# jussi.net
KiCad netlist of a schematic drawn in EAGLE
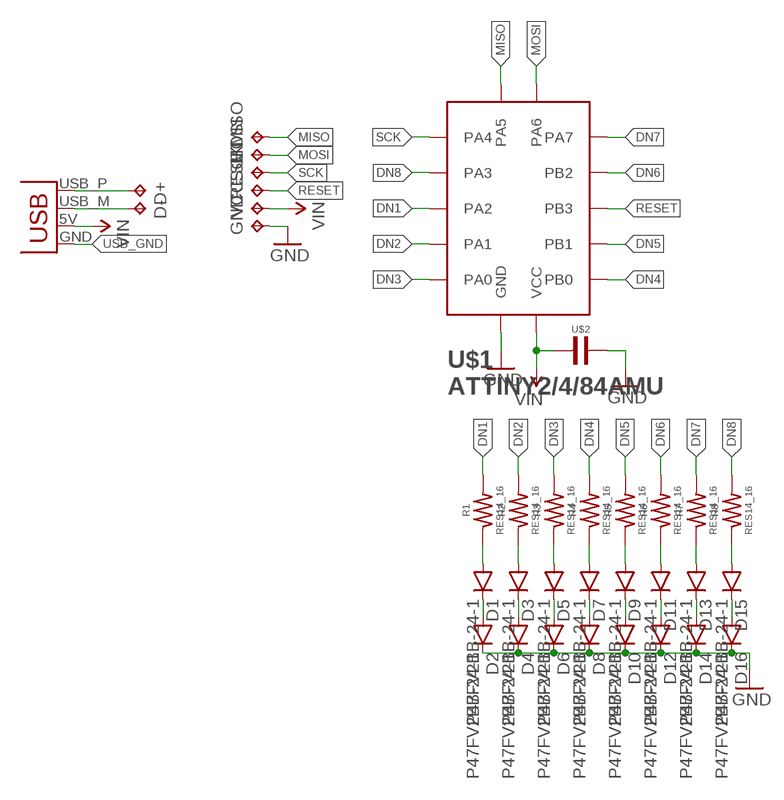
[diagram p0: schematic, sheet 1]

(export (version "E")
  (design (tool "Eeschema 10.0.6"))
  (components
    (comp (ref "D+")
      (value "TPTP08R")
      (footprint "eagle-import:TP08R")
      (libsource (lib "eagle-import") (part "TPTP08R"))
    )
    (comp (ref "D-")
      (value "TPTP08R")
      (footprint "eagle-import:TP08R")
      (libsource (lib "eagle-import") (part "TPTP08R"))
    )
    (comp (ref "D1")
      (value "P47FV2BB-24-1")
      (footprint "eagle-import:P47F")
      (fields
        (field (name "DIGIKEY_PART_#") "475-1301-1-ND")
        (field (name "MANUFACTURER") "OSRAM Opto Semiconductors Inc.")
        (field (name "MFG_PART_#") "LA P47F-V2BB-24-3A4B-Z")
      )
      (libsource (lib "eagle-import") (part "P47FV2BB-24-1"))
    )
    (comp (ref "D2")
      (value "P47FV2BB-24-1")
      (footprint "eagle-import:P47F")
      (fields
        (field (name "DIGIKEY_PART_#") "475-1301-1-ND")
        (field (name "MANUFACTURER") "OSRAM Opto Semiconductors Inc.")
        (field (name "MFG_PART_#") "LA P47F-V2BB-24-3A4B-Z")
      )
      (libsource (lib "eagle-import") (part "P47FV2BB-24-1"))
    )
    (comp (ref "D3")
      (value "P47FV2BB-24-1")
      (footprint "eagle-import:P47F")
      (fields
        (field (name "DIGIKEY_PART_#") "475-1301-1-ND")
        (field (name "MANUFACTURER") "OSRAM Opto Semiconductors Inc.")
        (field (name "MFG_PART_#") "LA P47F-V2BB-24-3A4B-Z")
      )
      (libsource (lib "eagle-import") (part "P47FV2BB-24-1"))
    )
    (comp (ref "D4")
      (value "P47FV2BB-24-1")
      (footprint "eagle-import:P47F")
      (fields
        (field (name "DIGIKEY_PART_#") "475-1301-1-ND")
        (field (name "MANUFACTURER") "OSRAM Opto Semiconductors Inc.")
        (field (name "MFG_PART_#") "LA P47F-V2BB-24-3A4B-Z")
      )
      (libsource (lib "eagle-import") (part "P47FV2BB-24-1"))
    )
    (comp (ref "D5")
      (value "P47FV2BB-24-1")
      (footprint "eagle-import:P47F")
      (fields
        (field (name "DIGIKEY_PART_#") "475-1301-1-ND")
        (field (name "MANUFACTURER") "OSRAM Opto Semiconductors Inc.")
        (field (name "MFG_PART_#") "LA P47F-V2BB-24-3A4B-Z")
      )
      (libsource (lib "eagle-import") (part "P47FV2BB-24-1"))
    )
    (comp (ref "D6")
      (value "P47FV2BB-24-1")
      (footprint "eagle-import:P47F")
      (fields
        (field (name "DIGIKEY_PART_#") "475-1301-1-ND")
        (field (name "MANUFACTURER") "OSRAM Opto Semiconductors Inc.")
        (field (name "MFG_PART_#") "LA P47F-V2BB-24-3A4B-Z")
      )
      (libsource (lib "eagle-import") (part "P47FV2BB-24-1"))
    )
    (comp (ref "D7")
      (value "P47FV2BB-24-1")
      (footprint "eagle-import:P47F")
      (fields
        (field (name "DIGIKEY_PART_#") "475-1301-1-ND")
        (field (name "MANUFACTURER") "OSRAM Opto Semiconductors Inc.")
        (field (name "MFG_PART_#") "LA P47F-V2BB-24-3A4B-Z")
      )
      (libsource (lib "eagle-import") (part "P47FV2BB-24-1"))
    )
    (comp (ref "D8")
      (value "P47FV2BB-24-1")
      (footprint "eagle-import:P47F")
      (fields
        (field (name "DIGIKEY_PART_#") "475-1301-1-ND")
        (field (name "MANUFACTURER") "OSRAM Opto Semiconductors Inc.")
        (field (name "MFG_PART_#") "LA P47F-V2BB-24-3A4B-Z")
      )
      (libsource (lib "eagle-import") (part "P47FV2BB-24-1"))
    )
    (comp (ref "D9")
      (value "P47FV2BB-24-1")
      (footprint "eagle-import:P47F")
      (fields
        (field (name "DIGIKEY_PART_#") "475-1301-1-ND")
        (field (name "MANUFACTURER") "OSRAM Opto Semiconductors Inc.")
        (field (name "MFG_PART_#") "LA P47F-V2BB-24-3A4B-Z")
      )
      (libsource (lib "eagle-import") (part "P47FV2BB-24-1"))
    )
    (comp (ref "D10")
      (value "P47FV2BB-24-1")
      (footprint "eagle-import:P47F")
      (fields
        (field (name "DIGIKEY_PART_#") "475-1301-1-ND")
        (field (name "MANUFACTURER") "OSRAM Opto Semiconductors Inc.")
        (field (name "MFG_PART_#") "LA P47F-V2BB-24-3A4B-Z")
      )
      (libsource (lib "eagle-import") (part "P47FV2BB-24-1"))
    )
    (comp (ref "D11")
      (value "P47FV2BB-24-1")
      (footprint "eagle-import:P47F")
      (fields
        (field (name "DIGIKEY_PART_#") "475-1301-1-ND")
        (field (name "MANUFACTURER") "OSRAM Opto Semiconductors Inc.")
        (field (name "MFG_PART_#") "LA P47F-V2BB-24-3A4B-Z")
      )
      (libsource (lib "eagle-import") (part "P47FV2BB-24-1"))
    )
    (comp (ref "D12")
      (value "P47FV2BB-24-1")
      (footprint "eagle-import:P47F")
      (fields
        (field (name "DIGIKEY_PART_#") "475-1301-1-ND")
        (field (name "MANUFACTURER") "OSRAM Opto Semiconductors Inc.")
        (field (name "MFG_PART_#") "LA P47F-V2BB-24-3A4B-Z")
      )
      (libsource (lib "eagle-import") (part "P47FV2BB-24-1"))
    )
    (comp (ref "D13")
      (value "P47FV2BB-24-1")
      (footprint "eagle-import:P47F")
      (fields
        (field (name "DIGIKEY_PART_#") "475-1301-1-ND")
        (field (name "MANUFACTURER") "OSRAM Opto Semiconductors Inc.")
        (field (name "MFG_PART_#") "LA P47F-V2BB-24-3A4B-Z")
      )
      (libsource (lib "eagle-import") (part "P47FV2BB-24-1"))
    )
    (comp (ref "D14")
      (value "P47FV2BB-24-1")
      (footprint "eagle-import:P47F")
      (fields
        (field (name "DIGIKEY_PART_#") "475-1301-1-ND")
        (field (name "MANUFACTURER") "OSRAM Opto Semiconductors Inc.")
        (field (name "MFG_PART_#") "LA P47F-V2BB-24-3A4B-Z")
      )
      (libsource (lib "eagle-import") (part "P47FV2BB-24-1"))
    )
    (comp (ref "D15")
      (value "P47FV2BB-24-1")
      (footprint "eagle-import:P47F")
      (fields
        (field (name "DIGIKEY_PART_#") "475-1301-1-ND")
        (field (name "MANUFACTURER") "OSRAM Opto Semiconductors Inc.")
        (field (name "MFG_PART_#") "LA P47F-V2BB-24-3A4B-Z")
      )
      (libsource (lib "eagle-import") (part "P47FV2BB-24-1"))
    )
    (comp (ref "D16")
      (value "P47FV2BB-24-1")
      (footprint "eagle-import:P47F")
      (fields
        (field (name "DIGIKEY_PART_#") "475-1301-1-ND")
        (field (name "MANUFACTURER") "OSRAM Opto Semiconductors Inc.")
        (field (name "MFG_PART_#") "LA P47F-V2BB-24-3A4B-Z")
      )
      (libsource (lib "eagle-import") (part "P47FV2BB-24-1"))
    )
    (comp (ref "GND")
      (value "TPTP08R")
      (footprint "eagle-import:TP08R")
      (libsource (lib "eagle-import") (part "TPTP08R"))
    )
    (comp (ref "JP1")
      (value "USBPCB")
      (footprint "eagle-import:USB-A-PCB")
      (libsource (lib "eagle-import") (part "USBPCB"))
    )
    (comp (ref "MISO")
      (value "TPTP08R")
      (footprint "eagle-import:TP08R")
      (libsource (lib "eagle-import") (part "TPTP08R"))
    )
    (comp (ref "MOSI")
      (value "TPTP08R")
      (footprint "eagle-import:TP08R")
      (libsource (lib "eagle-import") (part "TPTP08R"))
    )
    (comp (ref "R1")
      (value "RES14_16")
      (footprint "eagle-import:0402")
      (fields
        (field (name "DIGIKEY_PART_#") "541-14.0LCT-ND")
        (field (name "MANUFACTURER") "Vishay Dale")
        (field (name "MFG_PART_#") "CRCW040214R0FKED")
      )
      (libsource (lib "eagle-import") (part "RES14_16"))
    )
    (comp (ref "R2")
      (value "RES14_16")
      (footprint "eagle-import:0402")
      (fields
        (field (name "DIGIKEY_PART_#") "541-14.0LCT-ND")
        (field (name "MANUFACTURER") "Vishay Dale")
        (field (name "MFG_PART_#") "CRCW040214R0FKED")
      )
      (libsource (lib "eagle-import") (part "RES14_16"))
    )
    (comp (ref "R3")
      (value "RES14_16")
      (footprint "eagle-import:0402")
      (fields
        (field (name "DIGIKEY_PART_#") "541-14.0LCT-ND")
        (field (name "MANUFACTURER") "Vishay Dale")
        (field (name "MFG_PART_#") "CRCW040214R0FKED")
      )
      (libsource (lib "eagle-import") (part "RES14_16"))
    )
    (comp (ref "R4")
      (value "RES14_16")
      (footprint "eagle-import:0402")
      (fields
        (field (name "DIGIKEY_PART_#") "541-14.0LCT-ND")
        (field (name "MANUFACTURER") "Vishay Dale")
        (field (name "MFG_PART_#") "CRCW040214R0FKED")
      )
      (libsource (lib "eagle-import") (part "RES14_16"))
    )
    (comp (ref "R5")
      (value "RES14_16")
      (footprint "eagle-import:0402")
      (fields
        (field (name "DIGIKEY_PART_#") "541-14.0LCT-ND")
        (field (name "MANUFACTURER") "Vishay Dale")
        (field (name "MFG_PART_#") "CRCW040214R0FKED")
      )
      (libsource (lib "eagle-import") (part "RES14_16"))
    )
    (comp (ref "R6")
      (value "RES14_16")
      (footprint "eagle-import:0402")
      (fields
        (field (name "DIGIKEY_PART_#") "541-14.0LCT-ND")
        (field (name "MANUFACTURER") "Vishay Dale")
        (field (name "MFG_PART_#") "CRCW040214R0FKED")
      )
      (libsource (lib "eagle-import") (part "RES14_16"))
    )
    (comp (ref "R7")
      (value "RES14_16")
      (footprint "eagle-import:0402")
      (fields
        (field (name "DIGIKEY_PART_#") "541-14.0LCT-ND")
        (field (name "MANUFACTURER") "Vishay Dale")
        (field (name "MFG_PART_#") "CRCW040214R0FKED")
      )
      (libsource (lib "eagle-import") (part "RES14_16"))
    )
    (comp (ref "R8")
      (value "RES14_16")
      (footprint "eagle-import:0402")
      (fields
        (field (name "DIGIKEY_PART_#") "541-14.0LCT-ND")
        (field (name "MANUFACTURER") "Vishay Dale")
        (field (name "MFG_PART_#") "CRCW040214R0FKED")
      )
      (libsource (lib "eagle-import") (part "RES14_16"))
    )
    (comp (ref "RESET")
      (value "TPTP08R")
      (footprint "eagle-import:TP08R")
      (libsource (lib "eagle-import") (part "TPTP08R"))
    )
    (comp (ref "SCK")
      (value "TPTP08R")
      (footprint "eagle-import:TP08R")
      (libsource (lib "eagle-import") (part "TPTP08R"))
    )
    (comp (ref "U$1")
      (value "ATTINY2/4/84AMU")
      (footprint "eagle-import:20-WFQFN")
      (fields
        (field (name "DIGIKEY_PART_#") "ATTINY24A-MU-ND")
        (field (name "MANUFACTURER") "Atmel")
        (field (name "MFG_PART_#") "ATTINY24A-MU")
      )
      (libsource (lib "eagle-import") (part "ATTINY2/4/84AMU"))
    )
    (comp (ref "U$2")
      (value "CAP47UF_10V")
      (footprint "eagle-import:0805")
      (fields
        (field (name "DIGIKEY_PART_#") "445-8239-1-ND")
        (field (name "MANUFACTURER") "TDK Corporation")
        (field (name "MFG_PART_#") "C2012X5R1A476M125AC")
      )
      (libsource (lib "eagle-import") (part "CAP47UF_10V"))
    )
    (comp (ref "VCC")
      (value "TPTP08R")
      (footprint "eagle-import:TP08R")
      (libsource (lib "eagle-import") (part "TPTP08R"))
    )
  )
  (nets
    (net (code "1") (name "DN1") (class "Default")
      (node (ref "R1") (pin "2") (pinfunction "2_2") (pintype "passive"))
      (node (ref "U$1") (pin "3") (pinfunction "PA2_3") (pintype "passive"))
    )
    (net (code "2") (name "DN2") (class "Default")
      (node (ref "R2") (pin "2") (pinfunction "2_2") (pintype "passive"))
      (node (ref "U$1") (pin "4") (pinfunction "PA1_4") (pintype "passive"))
    )
    (net (code "3") (name "DN3") (class "Default")
      (node (ref "R3") (pin "2") (pinfunction "2_2") (pintype "passive"))
      (node (ref "U$1") (pin "5") (pinfunction "PA0_5") (pintype "passive"))
    )
    (net (code "4") (name "DN4") (class "Default")
      (node (ref "R4") (pin "2") (pinfunction "2_2") (pintype "passive"))
      (node (ref "U$1") (pin "11") (pinfunction "PB0_11") (pintype "passive"))
    )
    (net (code "5") (name "DN5") (class "Default")
      (node (ref "R5") (pin "2") (pinfunction "2_2") (pintype "passive"))
      (node (ref "U$1") (pin "12") (pinfunction "PB1_12") (pintype "passive"))
    )
    (net (code "6") (name "DN6") (class "Default")
      (node (ref "R6") (pin "2") (pinfunction "2_2") (pintype "passive"))
      (node (ref "U$1") (pin "14") (pinfunction "PB2_14") (pintype "passive"))
    )
    (net (code "7") (name "DN7") (class "Default")
      (node (ref "R7") (pin "2") (pinfunction "2_2") (pintype "passive"))
      (node (ref "U$1") (pin "15") (pinfunction "PA7_15") (pintype "passive"))
    )
    (net (code "8") (name "DN8") (class "Default")
      (node (ref "R8") (pin "2") (pinfunction "2_2") (pintype "passive"))
      (node (ref "U$1") (pin "2") (pinfunction "PA3_2") (pintype "passive"))
    )
    (net (code "9") (name "GND") (class "Default")
      (node (ref "D10") (pin "C") (pinfunction "C_C") (pintype "passive"))
      (node (ref "D12") (pin "C") (pinfunction "C_C") (pintype "passive"))
      (node (ref "D14") (pin "C") (pinfunction "C_C") (pintype "passive"))
      (node (ref "D16") (pin "C") (pinfunction "C_C") (pintype "passive"))
      (node (ref "D2") (pin "C") (pinfunction "C_C") (pintype "passive"))
      (node (ref "D4") (pin "C") (pinfunction "C_C") (pintype "passive"))
      (node (ref "D6") (pin "C") (pinfunction "C_C") (pintype "passive"))
      (node (ref "D8") (pin "C") (pinfunction "C_C") (pintype "passive"))
      (node (ref "GND") (pin "TP") (pinfunction "TP_TP") (pintype "input"))
      (node (ref "U$1") (pin "8") (pinfunction "GND_8") (pintype "passive"))
      (node (ref "U$1") (pin "PAD") (pinfunction "GND_PAD") (pintype "passive"))
      (node (ref "U$2") (pin "2") (pinfunction "2_2") (pintype "passive"))
    )
    (net (code "10") (name "MISO") (class "Default")
      (node (ref "MISO") (pin "TP") (pinfunction "TP_TP") (pintype "input"))
      (node (ref "U$1") (pin "20") (pinfunction "PA5_20") (pintype "passive"))
    )
    (net (code "11") (name "MOSI") (class "Default")
      (node (ref "MOSI") (pin "TP") (pinfunction "TP_TP") (pintype "input"))
      (node (ref "U$1") (pin "16") (pinfunction "PA6_16") (pintype "passive"))
    )
    (net (code "12") (name "Net-(D1-PadA)") (class "Default")
      (node (ref "D1") (pin "A") (pinfunction "A_A") (pintype "passive"))
      (node (ref "R1") (pin "1") (pinfunction "1_1") (pintype "passive"))
    )
    (net (code "13") (name "Net-(D1-PadC)") (class "Default")
      (node (ref "D1") (pin "C") (pinfunction "C_C") (pintype "passive"))
      (node (ref "D2") (pin "A") (pinfunction "A_A") (pintype "passive"))
    )
    (net (code "14") (name "Net-(D3-PadA)") (class "Default")
      (node (ref "D3") (pin "A") (pinfunction "A_A") (pintype "passive"))
      (node (ref "R2") (pin "1") (pinfunction "1_1") (pintype "passive"))
    )
    (net (code "15") (name "Net-(D3-PadC)") (class "Default")
      (node (ref "D3") (pin "C") (pinfunction "C_C") (pintype "passive"))
      (node (ref "D4") (pin "A") (pinfunction "A_A") (pintype "passive"))
    )
    (net (code "16") (name "Net-(D5-PadA)") (class "Default")
      (node (ref "D5") (pin "A") (pinfunction "A_A") (pintype "passive"))
      (node (ref "R3") (pin "1") (pinfunction "1_1") (pintype "passive"))
    )
    (net (code "17") (name "Net-(D5-PadC)") (class "Default")
      (node (ref "D5") (pin "C") (pinfunction "C_C") (pintype "passive"))
      (node (ref "D6") (pin "A") (pinfunction "A_A") (pintype "passive"))
    )
    (net (code "18") (name "Net-(D7-PadA)") (class "Default")
      (node (ref "D7") (pin "A") (pinfunction "A_A") (pintype "passive"))
      (node (ref "R4") (pin "1") (pinfunction "1_1") (pintype "passive"))
    )
    (net (code "19") (name "Net-(D7-PadC)") (class "Default")
      (node (ref "D7") (pin "C") (pinfunction "C_C") (pintype "passive"))
      (node (ref "D8") (pin "A") (pinfunction "A_A") (pintype "passive"))
    )
    (net (code "20") (name "Net-(D9-PadA)") (class "Default")
      (node (ref "D9") (pin "A") (pinfunction "A_A") (pintype "passive"))
      (node (ref "R5") (pin "1") (pinfunction "1_1") (pintype "passive"))
    )
    (net (code "21") (name "Net-(D10-PadA)") (class "Default")
      (node (ref "D10") (pin "A") (pinfunction "A_A") (pintype "passive"))
      (node (ref "D9") (pin "C") (pinfunction "C_C") (pintype "passive"))
    )
    (net (code "22") (name "Net-(D11-PadA)") (class "Default")
      (node (ref "D11") (pin "A") (pinfunction "A_A") (pintype "passive"))
      (node (ref "R6") (pin "1") (pinfunction "1_1") (pintype "passive"))
    )
    (net (code "23") (name "Net-(D11-PadC)") (class "Default")
      (node (ref "D11") (pin "C") (pinfunction "C_C") (pintype "passive"))
      (node (ref "D12") (pin "A") (pinfunction "A_A") (pintype "passive"))
    )
    (net (code "24") (name "Net-(D13-PadA)") (class "Default")
      (node (ref "D13") (pin "A") (pinfunction "A_A") (pintype "passive"))
      (node (ref "R7") (pin "1") (pinfunction "1_1") (pintype "passive"))
    )
    (net (code "25") (name "Net-(D13-PadC)") (class "Default")
      (node (ref "D13") (pin "C") (pinfunction "C_C") (pintype "passive"))
      (node (ref "D14") (pin "A") (pinfunction "A_A") (pintype "passive"))
    )
    (net (code "26") (name "Net-(D15-PadA)") (class "Default")
      (node (ref "D15") (pin "A") (pinfunction "A_A") (pintype "passive"))
      (node (ref "R8") (pin "1") (pinfunction "1_1") (pintype "passive"))
    )
    (net (code "27") (name "Net-(D15-PadC)") (class "Default")
      (node (ref "D15") (pin "C") (pinfunction "C_C") (pintype "passive"))
      (node (ref "D16") (pin "A") (pinfunction "A_A") (pintype "passive"))
    )
    (net (code "28") (name "Net-(JP1-D+)") (class "Default")
      (node (ref "D+") (pin "TP") (pinfunction "TP_TP") (pintype "input"))
      (node (ref "JP1") (pin "USB_P") (pinfunction "D+_USB_P") (pintype "bidirectional"))
    )
    (net (code "29") (name "Net-(JP1-D-)") (class "Default")
      (node (ref "D-") (pin "TP") (pinfunction "TP_TP") (pintype "input"))
      (node (ref "JP1") (pin "USB_M") (pinfunction "D-_USB_M") (pintype "bidirectional"))
    )
    (net (code "30") (name "RESET") (class "Default")
      (node (ref "RESET") (pin "TP") (pinfunction "TP_TP") (pintype "input"))
      (node (ref "U$1") (pin "13") (pinfunction "PB3_13") (pintype "passive"))
    )
    (net (code "31") (name "SCK") (class "Default")
      (node (ref "SCK") (pin "TP") (pinfunction "TP_TP") (pintype "input"))
      (node (ref "U$1") (pin "1") (pinfunction "PA4_1") (pintype "passive"))
    )
    (net (code "32") (name "USB_GND") (class "Default")
      (node (ref "JP1") (pin "GND") (pinfunction "GND_GND") (pintype "bidirectional"))
    )
    (net (code "33") (name "VIN") (class "Default")
      (node (ref "JP1") (pin "5V") (pinfunction "VBUS_5V") (pintype "bidirectional"))
      (node (ref "U$1") (pin "9") (pinfunction "VCC_9") (pintype "passive"))
      (node (ref "U$2") (pin "1") (pinfunction "1_1") (pintype "passive"))
      (node (ref "VCC") (pin "TP") (pinfunction "TP_TP") (pintype "input"))
    )
  )
)
